# Power_Supply_AC_to_DC.net
KiCad netlist of a schematic drawn in Altium Designer
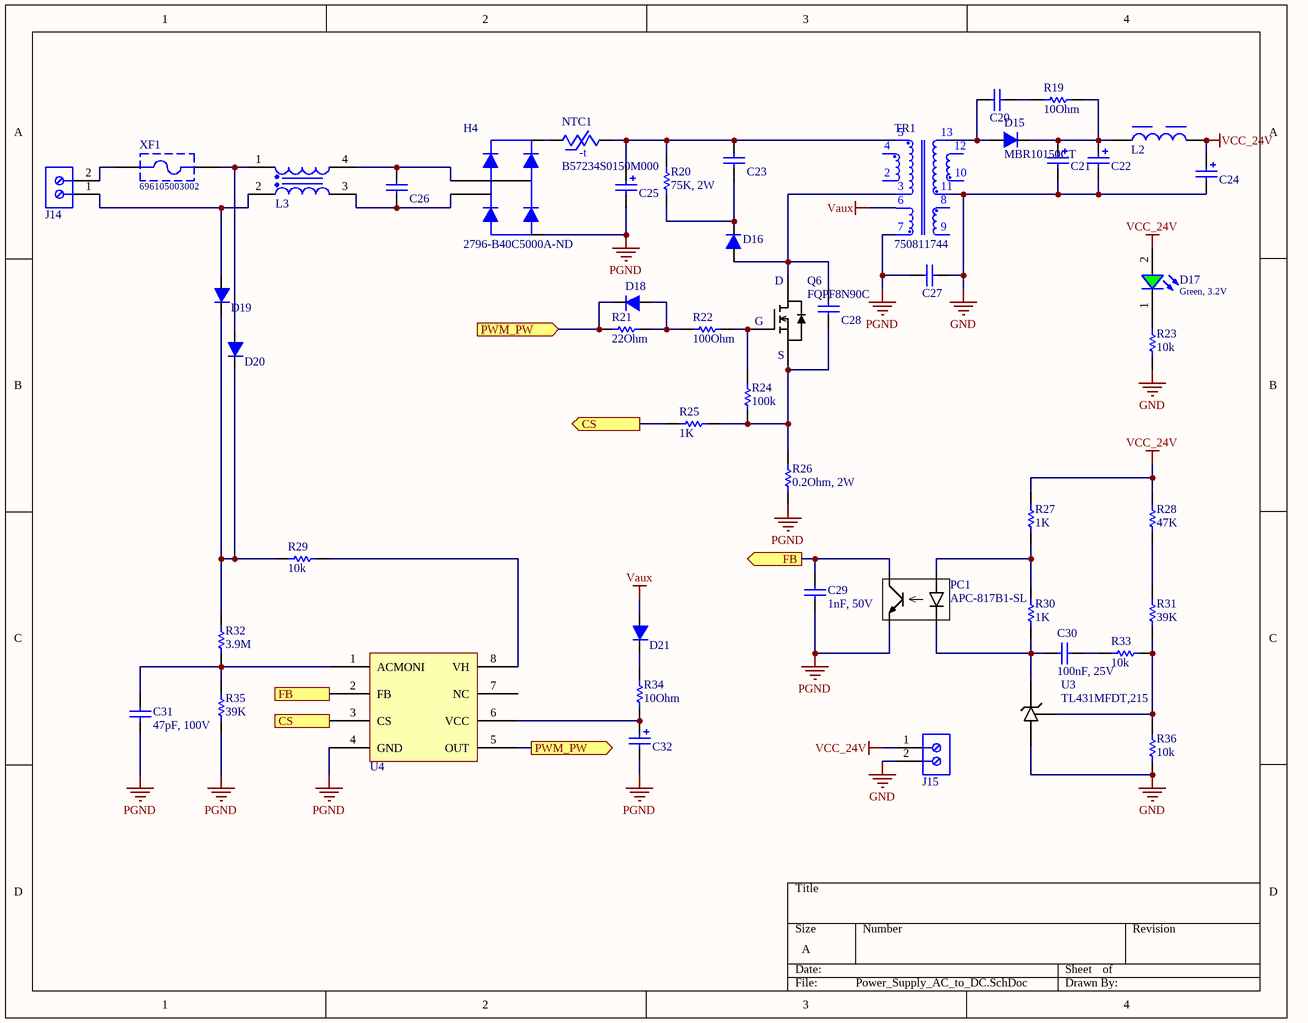
[diagram p0: Power_Supply_AC_to_DC.SchDoc]

(export (version "E")
  (design (tool "Eeschema 10.0.6"))
  (components
    (comp (ref "C20")
      (value "1nF")
      (footprint "WCAP-CSMH_0805_L2W1.25H0.8_Reflow")
      (fields
        (field (name "MANUFACTURER PART NUMBER") "885342207013")
        (field (name "MANUFACTURER") "Wurth Elektronik")
      )
      (libsource (lib "Altium_WCAP-CSMH (rev22c)") (part "885342207013"))
    )
    (comp (ref "C21")
      (value "1200uF")
      (footprint "WCAP-ATG8_D16H31.5")
      (description "WCAP-ATG8 Aluminum Electrolytic Capacitor, Radial THT, D16xH31.5mm, 1200uF, 63V")
      (fields
        (field (name "MANUFACTURER") "Wurth Elektronik")
        (field (name "MANUFACTURER PART NUMBER") "860010780025")
      )
      (libsource (lib "Altium_WCAP-ATG8 (rev22a)") (part "860010780025"))
    )
    (comp (ref "C22")
      (value "1200uF")
      (footprint "WCAP-ATG8_D16H31.5")
      (description "WCAP-ATG8 Aluminum Electrolytic Capacitor, Radial THT, D16xH31.5mm, 1200uF, 63V")
      (fields
        (field (name "MANUFACTURER") "Wurth Elektronik")
        (field (name "MANUFACTURER PART NUMBER") "860010780025")
      )
      (libsource (lib "Altium_WCAP-ATG8 (rev22a)") (part "860010780025"))
    )
    (comp (ref "C23")
      (value "4.7nF")
      (footprint "WCAP-CSMH_1206_L3.2W1.6H1.25")
      (fields
        (field (name "MANUFACTURER PART NUMBER") "885342208008")
        (field (name "MANUFACTURER") "Wurth Elektronik")
      )
      (libsource (lib "Altium_WCAP-CSMH (rev22c)") (part "885342208008"))
    )
    (comp (ref "C24")
      (value "100uF")
      (footprint "WCAP-ATG8_D8H11.5")
      (description "WCAP-ATG8 Aluminum Electrolytic Capacitor, Radial THT, D8xH11.5mm, 100uF, 50V")
      (fields
        (field (name "MANUFACTURER") "Wurth Elektronik")
        (field (name "MANUFACTURER PART NUMBER") "860010674014")
      )
      (libsource (lib "Altium_WCAP-ATG8 (rev22a)") (part "860010674014"))
    )
    (comp (ref "C25")
      (value "220uF")
      (footprint "WCAP-AI3H_D22H50")
      (description "WCAP-AI3H Aluminum Electrolytic Capacitor, Snap-In, D22xH50mm, 220uF, 450V")
      (fields
        (field (name "MANUFACTURER") "Wurth Elektronik")
        (field (name "MANUFACTURER PART NUMBER") "861141483007")
      )
      (libsource (lib "Altium_WCAP-AI3H (rev22a)") (part "861141483007"))
    )
    (comp (ref "C26")
      (value "2.2uF")
      (footprint "WCAP-FTX2_L26W15H25")
      (description "WCAP-FTX2 Film Capacitor, THT, L26W15H25mm, 2.2uF, 275VAC")
      (fields
        (field (name "MANUFACTURER") "Wurth Elektronik")
        (field (name "MANUFACTURER PART NUMBER") "890324026034")
      )
      (libsource (lib "Altium_WCAP-FTX2 (rev22a)") (part "890324026034"))
    )
    (comp (ref "C27")
      (value "2.2nF")
      (footprint "WCAP-CSSA_2211_L5.7W2.8H2.5")
      (description "WCAP-CSSA Multilayer Ceramic Chip Safety Capacitor, 2211, X7R Class II, X1/Y2, 2.2nF, 250VAC")
      (fields
        (field (name "MANUFACTURER") "Wurth Elektronik")
        (field (name "MANUFACTURER PART NUMBER") "8853522130151")
      )
      (libsource (lib "Altium_WCAP-CSSA (rev22a)") (part "8853522130151"))
    )
    (comp (ref "C28")
      (value "22pF")
      (footprint "WCAP-CSMH_1210_L3.2W2.5H0.95")
      (fields
        (field (name "MANUFACTURER PART NUMBER") "885342009002")
        (field (name "MANUFACTURER") "Wurth Elektronik")
      )
      (libsource (lib "Altium_WCAP-CSMH (rev22c)") (part "885342009002"))
    )
    (comp (ref "C29")
      (value "1nF, 50V")
      (footprint "WCAP-CSGP_0805_H=0.8mm_Reflow")
      (description "WCAP-CSGP Multilayer Ceramic Chip Capacitor, General Purpose, size 0805, NP0, 1nF, 50V")
      (fields
        (field (name "MANUFACTURER PART NUMBER") "885012007063")
        (field (name "MANUFACTURER") "Wurth Elektronik")
      )
      (libsource (lib "Altium_WCAP-CSGP (rev20a)") (part "885012007063"))
    )
    (comp (ref "C30")
      (value "100nF, 25V")
      (footprint "WCAP-CSGP_0805_H=0.8mm_Reflow")
      (description "WCAP-CSGP Multilayer Ceramic Chip Capacitor, General Purpose, size 0805, X7R, 100nF, 25V")
      (fields
        (field (name "MANUFACTURER PART NUMBER") "885012207072")
        (field (name "MANUFACTURER") "Wurth Elektronik")
      )
      (libsource (lib "Altium_WCAP-CSGP (rev20a)") (part "885012207072"))
    )
    (comp (ref "C31")
      (value "47pF, 100V")
      (footprint "WCAP-CSGP_0805_H=0.6mm_Reflow")
      (description "WCAP-CSGP Multilayer Ceramic Chip Capacitor, General Purpose, size 0805, NP0, 47pF, 100V")
      (fields
        (field (name "MANUFACTURER PART NUMBER") "885012007080")
        (field (name "MANUFACTURER") "Wurth Elektronik")
      )
      (libsource (lib "Altium_WCAP-CSGP (rev20a)") (part "885012007080"))
    )
    (comp (ref "C32")
      (value "10uF")
      (footprint "WCAP-ATG8_D5H11")
      (description "WCAP-ATG8 Aluminum Electrolytic Capacitor, Radial THT, D5xH11mm, 10uF, 50V")
      (fields
        (field (name "MANUFACTURER") "Wurth Elektronik")
        (field (name "MANUFACTURER PART NUMBER") "860010672009")
      )
      (libsource (lib "Altium_WCAP-ATG8 (rev22a)") (part "860010672009"))
    )
    (comp (ref "D15")
      (value "MBR10150CT")
      (footprint "MBR10150CT")
      (description "DIODE ARRAY SCHOTTKY 150V TO220")
      (fields (field (name "MFR") "SMC Diode Solutions"))
      (libsource (lib "YenDoo") (part "Diode"))
    )
    (comp (ref "D16")
      (value "RS1M-13-F")
      (footprint "SMA")
      (description "DIODE GEN PURP 1KV 1A SMA")
      (fields (field (name "MFR") "Diodes Incorporated"))
      (libsource (lib "YenDoo") (part "Diode"))
    )
    (comp (ref "D17")
      (value "Green, 3.2V")
      (footprint "WL-SMCW_0603_H=0.7mm")
      (description "WL-SMCW SMT Mono-color Chip LED Waterclear, size 0603, Green, 3.2V, 140deg")
      (fields (field (name "PART NUMBER") "150060GS75000") (field (name "PUBLISHER") "Wurth Elektronik"))
      (libsource (lib "Altium_WL-SMCW (rev20a)") (part "150060GS75000"))
    )
    (comp (ref "D18")
      (value "CDBA360-HF")
      (footprint "SMA")
      (description "DIODE SCHOTTKY 60V 3A DO214AC")
      (fields (field (name "MFR") "Comchip Technology"))
      (libsource (lib "YenDoo") (part "Diode"))
    )
    (comp (ref "D19")
      (value "RFU02VSM8STR")
      (footprint "Flat Lead")
      (description "DIODE GP 800V 200MA TUMD2SM")
      (fields (field (name "MFR") "Rohm Semiconductor"))
      (libsource (lib "YenDoo") (part "Diode"))
    )
    (comp (ref "D20")
      (value "RFU02VSM8STR")
      (footprint "Flat Lead")
      (description "DIODE GP 800V 200MA TUMD2SM")
      (fields (field (name "MFR") "Rohm Semiconductor"))
      (libsource (lib "YenDoo") (part "Diode"))
    )
    (comp (ref "D21")
      (value "RS1M-13-F")
      (footprint "SMA")
      (description "DIODE GEN PURP 1KV 1A SMA")
      (fields (field (name "MFR") "Diodes Incorporated"))
      (libsource (lib "YenDoo") (part "Diode"))
    )
    (comp (ref "H4")
      (value "2796-B40C5000A-ND")
      (footprint "GBJ-4")
      (description "Bridge Rectifier Single Phase Standard 80 V Through Hole 4-SIP")
      (libsource (lib "YenDoo") (part "H Bridge"))
    )
    (comp (ref "J14")
      (value "691137710002")
      (footprint "691137710002")
      (description "WR-TBL Series 1377 Horizontal Entry, Through Hole, pitch 5mm, 2p")
      (fields (field (name "MANUFACTURER") "Wurth Elektronik"))
      (libsource (lib "Altium_WR-TBL (rev22a)") (part "691137710002"))
    )
    (comp (ref "J15")
      (value "691137710002")
      (footprint "691137710002")
      (description "WR-TBL Series 1377 Horizontal Entry, Through Hole, pitch 5mm, 2p")
      (fields (field (name "MANUFACTURER") "Wurth Elektronik"))
      (libsource (lib "Altium_WR-TBL (rev22a)") (part "691137710002"))
    )
    (comp (ref "L2")
      (value "10µH, 7A")
      (footprint "WE-LHMI_1040")
      (description "WE-LHMI SMT Power Inductor, size 1040, 10µH, 7A, 30mΩ")
      (fields
        (field (name "MANUFACTURER PART NUMBER") "74437368100")
        (field (name "MANUFACTURER") "Wurth Elektronik")
      )
      (libsource (lib "WE-LHMI (rev22a)") (part "74437368100"))
    )
    (comp (ref "L3")
      (value "13mH")
      (footprint "WE-FC_UT20V")
      (description "WE-FC THT Common Mode Power Line Choke, UT20V, 13mH, 0.8A, 0.708Ω")
      (fields
        (field (name "MANUFACTURER PART NUMBER") "7448640415")
        (field (name "MANUFACTURER") "Wurth Elektronik")
      )
      (libsource (lib "WE-FC (rev22a)") (part "7448640415"))
    )
    (comp (ref "NTC1")
      (value "B57234S0150M000")
      (footprint "NTC")
      (description "THERMISTOR NTC 15OHM 3000K")
      (fields (field (name "MFR") "EPCOS - TDK Electronics") (field (name "TOLERANCE") "±20%"))
      (libsource (lib "YenDoo") (part "NTC"))
    )
    (comp (ref "PC1")
      (value "APC-817B1-SL")
      (footprint "APC-817B1-SL")
      (description "DIP4, DC INPUT, PHOTO TRANSISTOR")
      (fields (field (name "MFR") "American Bright Optoelectronics Corporation"))
      (libsource (lib "YenDoo") (part "Opto Isolator"))
    )
    (comp (ref "Q6")
      (value "FQPF8N90C")
      (footprint "FQPF8N90C")
      (description "MOSFET N-CH 900V 6.3A TO220F")
      (fields (field (name "MFR") "onsemi"))
      (libsource (lib "YenDoo") (part "Mosfet"))
    )
    (comp (ref "R19")
      (value "10Ohm")
      (footprint "RES-SM-2512")
      (description "RES 10 OHM 0.5% 1W 2512")
      (fields (field (name "MFR") "KOA Speer Electronics, Inc.") (field (name "TOLERANCE") "±0.5%"))
      (libsource (lib "PIF_Library") (part "RESISTOR SMD"))
    )
    (comp (ref "R20")
      (value "75K, 2W")
      (footprint "RES-SM-2512")
      (description "RES SMD 75K OHM 1% 2W 2512")
      (fields (field (name "MFR") "TE Connectivity Passive Product") (field (name "TOLERANCE") "±1%"))
      (libsource (lib "PIF_Library") (part "RESISTOR SMD"))
    )
    (comp (ref "R21")
      (value "22Ohm")
      (footprint "RES-SM-0805")
      (description "RES 22 OHM 1% 1/4W 0805")
      (fields (field (name "MFR") "KOA Speer Electronics, Inc.") (field (name "TOLERANCE") "±1%"))
      (libsource (lib "PIF_Library") (part "RESISTOR SMD"))
    )
    (comp (ref "R22")
      (value "100Ohm")
      (footprint "RES-SM-0805")
      (description "RES 100 OHM 5% 1/4W 0805")
      (fields (field (name "MFR") "KOA Speer Electronics, Inc.") (field (name "TOLERANCE") "±5%"))
      (libsource (lib "PIF_Library") (part "RESISTOR SMD"))
    )
    (comp (ref "R23")
      (value "10k")
      (footprint "RES-SM-0805")
      (description "RES 10K OHM 1% 1/4W 0805")
      (fields (field (name "MFR") "KOA Speer Electronics, Inc.") (field (name "TOLERANCE") "±1%"))
      (libsource (lib "PIF_Library") (part "RESISTOR SMD"))
    )
    (comp (ref "R24")
      (value "100k")
      (footprint "RES-SM-0805")
      (description "RES 100K OHM 1% 1/4W 0805")
      (fields (field (name "MFR") "KOA Speer Electronics, Inc.") (field (name "TOLERANCE") "±1%"))
      (libsource (lib "PIF_Library") (part "RESISTOR SMD"))
    )
    (comp (ref "R25")
      (value "1K")
      (footprint "RES-SM-0805")
      (description "RES 1K OHM 5% 1/4W 0805")
      (fields (field (name "MFR") "KOA Speer Electronics, Inc.") (field (name "TOLERANCE") "±5%"))
      (libsource (lib "PIF_Library") (part "RESISTOR SMD"))
    )
    (comp (ref "R26")
      (value "0.2Ohm, 2W")
      (footprint "RES-SM-2010")
      (description "RES 0.2 OHM 2.0 W 1% 2010 SMD")
      (fields (field (name "MFR") "Vishay Dale") (field (name "TOLERANCE") "±1%"))
      (libsource (lib "PIF_Library") (part "RESISTOR SMD"))
    )
    (comp (ref "R27")
      (value "1K")
      (footprint "RES-SM-0805")
      (description "RES 1K OHM 5% 1/4W 0805")
      (fields (field (name "MFR") "KOA Speer Electronics, Inc.") (field (name "TOLERANCE") "±5%"))
      (libsource (lib "PIF_Library") (part "RESISTOR SMD"))
    )
    (comp (ref "R28")
      (value "47K")
      (footprint "RES-SM-0805")
      (description "RES 47K OHM 5% 1/4W 0805")
      (fields (field (name "MFR") "KOA Speer Electronics, Inc.") (field (name "TOLERANCE") "±5%"))
      (libsource (lib "PIF_Library") (part "RESISTOR SMD"))
    )
    (comp (ref "R29")
      (value "10k")
      (footprint "RES-SM-0805")
      (description "RES 10K OHM 1% 1/4W 0805")
      (fields (field (name "MFR") "KOA Speer Electronics, Inc.") (field (name "TOLERANCE") "±1%"))
      (libsource (lib "PIF_Library") (part "RESISTOR SMD"))
    )
    (comp (ref "R30")
      (value "1K")
      (footprint "RES-SM-0805")
      (description "RES 1K OHM 5% 1/4W 0805")
      (fields (field (name "MFR") "KOA Speer Electronics, Inc.") (field (name "TOLERANCE") "±5%"))
      (libsource (lib "PIF_Library") (part "RESISTOR SMD"))
    )
    (comp (ref "R31")
      (value "39K")
      (footprint "RES-SM-0805")
      (description "RES 39K OHM 5% 1/4W 0805")
      (fields (field (name "MFR") "KOA Speer Electronics, Inc.") (field (name "TOLERANCE") "±5%"))
      (libsource (lib "PIF_Library") (part "RESISTOR SMD"))
    )
    (comp (ref "R32")
      (value "3.9M")
      (footprint "RES-SM-0805")
      (description "RES 3.9M OHM 5% 1/4W 0805")
      (fields (field (name "MFR") "KOA Speer Electronics, Inc.") (field (name "TOLERANCE") "±5%"))
      (libsource (lib "PIF_Library") (part "RESISTOR SMD"))
    )
    (comp (ref "R33")
      (value "10k")
      (footprint "RES-SM-0805")
      (description "RES 10K OHM 1% 1/4W 0805")
      (fields (field (name "MFR") "KOA Speer Electronics, Inc.") (field (name "TOLERANCE") "±1%"))
      (libsource (lib "PIF_Library") (part "RESISTOR SMD"))
    )
    (comp (ref "R34")
      (value "10Ohm")
      (footprint "RES-SM-0805")
      (description "RES 10 OHM 1% 1/4W 0805")
      (fields (field (name "MFR") "KOA Speer Electronics, Inc.") (field (name "TOLERANCE") "±1%"))
      (libsource (lib "PIF_Library") (part "RESISTOR SMD"))
    )
    (comp (ref "R35")
      (value "39K")
      (footprint "RES-SM-0805")
      (description "RES 39K OHM 5% 1/4W 0805")
      (fields (field (name "MFR") "KOA Speer Electronics, Inc.") (field (name "TOLERANCE") "±5%"))
      (libsource (lib "PIF_Library") (part "RESISTOR SMD"))
    )
    (comp (ref "R36")
      (value "10k")
      (footprint "RES-SM-0805")
      (description "RES 10K OHM 1% 1/4W 0805")
      (fields (field (name "MFR") "KOA Speer Electronics, Inc.") (field (name "TOLERANCE") "±1%"))
      (libsource (lib "PIF_Library") (part "RESISTOR SMD"))
    )
    (comp (ref "TR1")
      (value "750811744")
      (footprint "750811744")
      (description "Flyback Converters For For DC/DC Converters SMPS Transformer 4000Vrms Isolation 80kHz Through Hole")
      (fields (field (name "MFR") "Würth Elektronik"))
      (libsource (lib "YenDoo") (part "750811744"))
    )
    (comp (ref "U3")
      (value "TL431MFDT,215")
      (footprint "TO-236AB")
      (description "IC VREF SHUNT ADJ 2% TO236AB")
      (fields (field (name "MFR") "Nexperia USA Inc.") (field (name "TOLERANCE") "±2%"))
      (libsource (lib "YenDoo") (part "IC Shunt"))
    )
    (comp (ref "U4")
      (value "BM1P061FJ-E2")
      (footprint "SOP-J8")
      (description "IC OFFLINE SWITCH FLYBACK 8SOPJ")
      (fields (field (name "MFR") "Rohm Semiconductor"))
      (libsource (lib "YenDoo") (part "IC PWM"))
    )
    (comp (ref "XF1")
      (value "696105003002")
      (footprint "696105003002")
      (description "WR-FSH Fuseholder THT Blocks PCB Clip Cover")
      (fields (field (name "MANUFACTURER") "Wurth Elektronik"))
      (libsource (lib "Altium_WR-FSH (rev21a)") (part "696105003002"))
    )
  )
  (nets
    (net (code "1") (name "/CS") (class "Default")
      (node (ref "R25") (pin "2") (pinfunction "2_2") (pintype "passive"))
      (node (ref "U4") (pin "3") (pinfunction "CS_3") (pintype "passive"))
    )
    (net (code "2") (name "/FB") (class "Default")
      (node (ref "C29") (pin "2") (pinfunction "2_2") (pintype "passive"))
      (node (ref "PC1") (pin "4") (pinfunction "4_4") (pintype "passive"))
      (node (ref "U4") (pin "2") (pinfunction "FB_2") (pintype "passive"))
    )
    (net (code "3") (name "/PWM_PW") (class "Default")
      (node (ref "D18") (pin "2") (pinfunction "K_2") (pintype "passive"))
      (node (ref "R21") (pin "1") (pinfunction "1_1") (pintype "passive"))
      (node (ref "U4") (pin "5") (pinfunction "OUT_5") (pintype "passive"))
    )
    (net (code "4") (name "GND") (class "Default")
      (node (ref "C21") (pin "2") (pinfunction "N_2") (pintype "passive"))
      (node (ref "C22") (pin "2") (pinfunction "N_2") (pintype "passive"))
      (node (ref "C24") (pin "2") (pinfunction "N_2") (pintype "passive"))
      (node (ref "C27") (pin "1") (pinfunction "1_1") (pintype "passive"))
      (node (ref "J15") (pin "2") (pinfunction "2_2") (pintype "passive"))
      (node (ref "R23") (pin "2") (pinfunction "2_2") (pintype "passive"))
      (node (ref "R36") (pin "2") (pinfunction "2_2") (pintype "passive"))
      (node (ref "TR1") (pin "11") (pinfunction "11_11") (pintype "passive"))
      (node (ref "U3") (pin "3") (pinfunction "3_3") (pintype "passive"))
    )
    (net (code "5") (name "Net-(C20-Pad2)") (class "Default")
      (node (ref "C20") (pin "2") (pinfunction "2_2") (pintype "passive"))
      (node (ref "R19") (pin "1") (pinfunction "1_1") (pintype "passive"))
    )
    (net (code "6") (name "Net-(C21-P)") (class "Default")
      (node (ref "C21") (pin "1") (pinfunction "P_1") (pintype "passive"))
      (node (ref "C22") (pin "1") (pinfunction "P_1") (pintype "passive"))
      (node (ref "D15") (pin "2") (pinfunction "K_2") (pintype "passive"))
      (node (ref "L2") (pin "1") (pinfunction "1_1") (pintype "passive"))
      (node (ref "R19") (pin "2") (pinfunction "2_2") (pintype "passive"))
    )
    (net (code "7") (name "Net-(C25-P)") (class "Default")
      (node (ref "C23") (pin "2") (pinfunction "2_2") (pintype "passive"))
      (node (ref "C25") (pin "1") (pinfunction "P_1") (pintype "passive"))
      (node (ref "NTC1") (pin "2") (pinfunction "2_2") (pintype "passive"))
      (node (ref "R20") (pin "2") (pinfunction "2_2") (pintype "passive"))
      (node (ref "TR1") (pin "5") (pinfunction "5_5") (pintype "passive"))
    )
    (net (code "8") (name "Net-(C26-Pad1)") (class "Default")
      (node (ref "C26") (pin "1") (pinfunction "1_1") (pintype "passive"))
      (node (ref "H4") (pin "3") (pinfunction "~_3") (pintype "passive"))
      (node (ref "L3") (pin "3") (pinfunction "3_3") (pintype "passive"))
    )
    (net (code "9") (name "Net-(C26-Pad2)") (class "Default")
      (node (ref "C26") (pin "2") (pinfunction "2_2") (pintype "passive"))
      (node (ref "H4") (pin "2") (pinfunction "~_2") (pintype "passive"))
      (node (ref "L3") (pin "4") (pinfunction "4_4") (pintype "passive"))
    )
    (net (code "10") (name "Net-(C30-Pad1)") (class "Default")
      (node (ref "C30") (pin "1") (pinfunction "1_1") (pintype "passive"))
      (node (ref "PC1") (pin "2") (pinfunction "2_2") (pintype "passive"))
      (node (ref "R30") (pin "2") (pinfunction "2_2") (pintype "passive"))
      (node (ref "U3") (pin "1") (pinfunction "1_1") (pintype "passive"))
    )
    (net (code "11") (name "Net-(C30-Pad2)") (class "Default")
      (node (ref "C30") (pin "2") (pinfunction "2_2") (pintype "passive"))
      (node (ref "R33") (pin "1") (pinfunction "1_1") (pintype "passive"))
    )
    (net (code "12") (name "Net-(C32-P)") (class "Default")
      (node (ref "C32") (pin "1") (pinfunction "P_1") (pintype "passive"))
      (node (ref "R34") (pin "1") (pinfunction "1_1") (pintype "passive"))
      (node (ref "U4") (pin "6") (pinfunction "VCC_6") (pintype "passive"))
    )
    (net (code "13") (name "Net-(D15-A)") (class "Default")
      (node (ref "C20") (pin "1") (pinfunction "1_1") (pintype "passive"))
      (node (ref "D15") (pin "1") (pinfunction "A_1") (pintype "passive"))
      (node (ref "TR1") (pin "13") (pinfunction "13_13") (pintype "passive"))
    )
    (net (code "14") (name "Net-(D16-A)") (class "Default")
      (node (ref "C28") (pin "2") (pinfunction "2_2") (pintype "passive"))
      (node (ref "D16") (pin "1") (pinfunction "A_1") (pintype "passive"))
      (node (ref "Q6") (pin "2") (pinfunction "D_2") (pintype "passive"))
      (node (ref "TR1") (pin "3") (pinfunction "3_3") (pintype "passive"))
    )
    (net (code "15") (name "Net-(D16-K)") (class "Default")
      (node (ref "C23") (pin "1") (pinfunction "1_1") (pintype "passive"))
      (node (ref "D16") (pin "2") (pinfunction "K_2") (pintype "passive"))
      (node (ref "R20") (pin "1") (pinfunction "1_1") (pintype "passive"))
    )
    (net (code "16") (name "Net-(D17-K)") (class "Default")
      (node (ref "D17") (pin "1") (pinfunction "K_1") (pintype "passive"))
      (node (ref "R23") (pin "1") (pinfunction "1_1") (pintype "passive"))
    )
    (net (code "17") (name "Net-(D18-A)") (class "Default")
      (node (ref "D18") (pin "1") (pinfunction "A_1") (pintype "passive"))
      (node (ref "R21") (pin "2") (pinfunction "2_2") (pintype "passive"))
      (node (ref "R22") (pin "1") (pinfunction "1_1") (pintype "passive"))
    )
    (net (code "18") (name "Net-(D19-A)") (class "Default")
      (node (ref "D19") (pin "1") (pinfunction "A_1") (pintype "passive"))
      (node (ref "J14") (pin "1") (pinfunction "1_1") (pintype "passive"))
      (node (ref "L3") (pin "2") (pinfunction "2_2") (pintype "passive"))
    )
    (net (code "19") (name "Net-(D19-K)") (class "Default")
      (node (ref "D19") (pin "2") (pinfunction "K_2") (pintype "passive"))
      (node (ref "D20") (pin "2") (pinfunction "K_2") (pintype "passive"))
      (node (ref "R29") (pin "2") (pinfunction "2_2") (pintype "passive"))
      (node (ref "R32") (pin "2") (pinfunction "2_2") (pintype "passive"))
    )
    (net (code "20") (name "Net-(D20-A)") (class "Default")
      (node (ref "D20") (pin "1") (pinfunction "A_1") (pintype "passive"))
      (node (ref "L3") (pin "1") (pinfunction "1_1") (pintype "passive"))
      (node (ref "XF1") (pin "2") (pinfunction "2_2") (pintype "passive"))
    )
    (net (code "21") (name "Net-(D21-K)") (class "Default")
      (node (ref "D21") (pin "2") (pinfunction "K_2") (pintype "passive"))
      (node (ref "R34") (pin "2") (pinfunction "2_2") (pintype "passive"))
    )
    (net (code "22") (name "Net-(H4-+)") (class "Default")
      (node (ref "H4") (pin "1") (pinfunction "+_1") (pintype "passive"))
      (node (ref "NTC1") (pin "1") (pinfunction "1_1") (pintype "passive"))
    )
    (net (code "23") (name "Net-(J14-Pad2)") (class "Default")
      (node (ref "J14") (pin "2") (pinfunction "2_2") (pintype "passive"))
      (node (ref "XF1") (pin "1") (pinfunction "1_1") (pintype "passive"))
    )
    (net (code "24") (name "Net-(PC1-Pad1)") (class "Default")
      (node (ref "PC1") (pin "1") (pinfunction "1_1") (pintype "passive"))
      (node (ref "R27") (pin "2") (pinfunction "2_2") (pintype "passive"))
      (node (ref "R30") (pin "1") (pinfunction "1_1") (pintype "passive"))
    )
    (net (code "25") (name "Net-(Q6-G)") (class "Default")
      (node (ref "Q6") (pin "1") (pinfunction "G_1") (pintype "passive"))
      (node (ref "R22") (pin "2") (pinfunction "2_2") (pintype "passive"))
      (node (ref "R24") (pin "2") (pinfunction "2_2") (pintype "passive"))
    )
    (net (code "26") (name "Net-(Q6-S)") (class "Default")
      (node (ref "C28") (pin "1") (pinfunction "1_1") (pintype "passive"))
      (node (ref "Q6") (pin "3") (pinfunction "S_3") (pintype "passive"))
      (node (ref "R24") (pin "1") (pinfunction "1_1") (pintype "passive"))
      (node (ref "R25") (pin "1") (pinfunction "1_1") (pintype "passive"))
      (node (ref "R26") (pin "2") (pinfunction "2_2") (pintype "passive"))
    )
    (net (code "27") (name "Net-(R28-Pad1)") (class "Default")
      (node (ref "R28") (pin "1") (pinfunction "1_1") (pintype "passive"))
      (node (ref "R31") (pin "2") (pinfunction "2_2") (pintype "passive"))
    )
    (net (code "28") (name "Net-(R31-Pad1)") (class "Default")
      (node (ref "R31") (pin "1") (pinfunction "1_1") (pintype "passive"))
      (node (ref "R33") (pin "2") (pinfunction "2_2") (pintype "passive"))
      (node (ref "R36") (pin "1") (pinfunction "1_1") (pintype "passive"))
      (node (ref "U3") (pin "2") (pinfunction "2_2") (pintype "passive"))
    )
    (net (code "29") (name "Net-(U4-ACMONI)") (class "Default")
      (node (ref "C31") (pin "2") (pinfunction "2_2") (pintype "passive"))
      (node (ref "R32") (pin "1") (pinfunction "1_1") (pintype "passive"))
      (node (ref "R35") (pin "2") (pinfunction "2_2") (pintype "passive"))
      (node (ref "U4") (pin "1") (pinfunction "ACMONI_1") (pintype "passive"))
    )
    (net (code "30") (name "Net-(U4-VH)") (class "Default")
      (node (ref "R29") (pin "1") (pinfunction "1_1") (pintype "passive"))
      (node (ref "U4") (pin "8") (pinfunction "VH_8") (pintype "passive"))
    )
    (net (code "31") (name "PGND") (class "Default")
      (node (ref "C25") (pin "2") (pinfunction "N_2") (pintype "passive"))
      (node (ref "C27") (pin "2") (pinfunction "2_2") (pintype "passive"))
      (node (ref "C29") (pin "1") (pinfunction "1_1") (pintype "passive"))
      (node (ref "C31") (pin "1") (pinfunction "1_1") (pintype "passive"))
      (node (ref "C32") (pin "2") (pinfunction "N_2") (pintype "passive"))
      (node (ref "H4") (pin "4") (pinfunction "-_4") (pintype "passive"))
      (node (ref "PC1") (pin "3") (pinfunction "3_3") (pintype "passive"))
      (node (ref "R26") (pin "1") (pinfunction "1_1") (pintype "passive"))
      (node (ref "R35") (pin "1") (pinfunction "1_1") (pintype "passive"))
      (node (ref "TR1") (pin "7") (pinfunction "7_7") (pintype "passive"))
      (node (ref "U4") (pin "4") (pinfunction "GND_4") (pintype "passive"))
    )
    (net (code "32") (name "VCC_24V") (class "Default")
      (node (ref "C24") (pin "1") (pinfunction "P_1") (pintype "passive"))
      (node (ref "D17") (pin "2") (pinfunction "A_2") (pintype "passive"))
      (node (ref "J15") (pin "1") (pinfunction "1_1") (pintype "passive"))
      (node (ref "L2") (pin "2") (pinfunction "2_2") (pintype "passive"))
      (node (ref "R27") (pin "1") (pinfunction "1_1") (pintype "passive"))
      (node (ref "R28") (pin "2") (pinfunction "2_2") (pintype "passive"))
    )
    (net (code "33") (name "Vaux") (class "Default")
      (node (ref "D21") (pin "1") (pinfunction "A_1") (pintype "passive"))
      (node (ref "TR1") (pin "6") (pinfunction "6_6") (pintype "passive"))
    )
    (net (code "34") (name "unconnected-(TR1-Pad2)") (class "Default")
      (node (ref "TR1") (pin "2") (pinfunction "2_2") (pintype "passive"))
    )
    (net (code "35") (name "unconnected-(TR1-Pad4)") (class "Default")
      (node (ref "TR1") (pin "4") (pinfunction "4_4") (pintype "passive"))
    )
    (net (code "36") (name "unconnected-(TR1-Pad8)") (class "Default")
      (node (ref "TR1") (pin "8") (pinfunction "8_8") (pintype "passive"))
    )
    (net (code "37") (name "unconnected-(TR1-Pad9)") (class "Default")
      (node (ref "TR1") (pin "9") (pinfunction "9_9") (pintype "passive"))
    )
    (net (code "38") (name "unconnected-(TR1-Pad10)") (class "Default")
      (node (ref "TR1") (pin "10") (pinfunction "10_10") (pintype "passive"))
    )
    (net (code "39") (name "unconnected-(TR1-Pad12)") (class "Default")
      (node (ref "TR1") (pin "12") (pinfunction "12_12") (pintype "passive"))
    )
    (net (code "40") (name "unconnected-(U4-NC-Pad7)") (class "Default")
      (node (ref "U4") (pin "7") (pinfunction "NC_7") (pintype "passive"))
    )
  )
)
